# Ver3.net
KiCad netlist of a schematic drawn in EAGLE
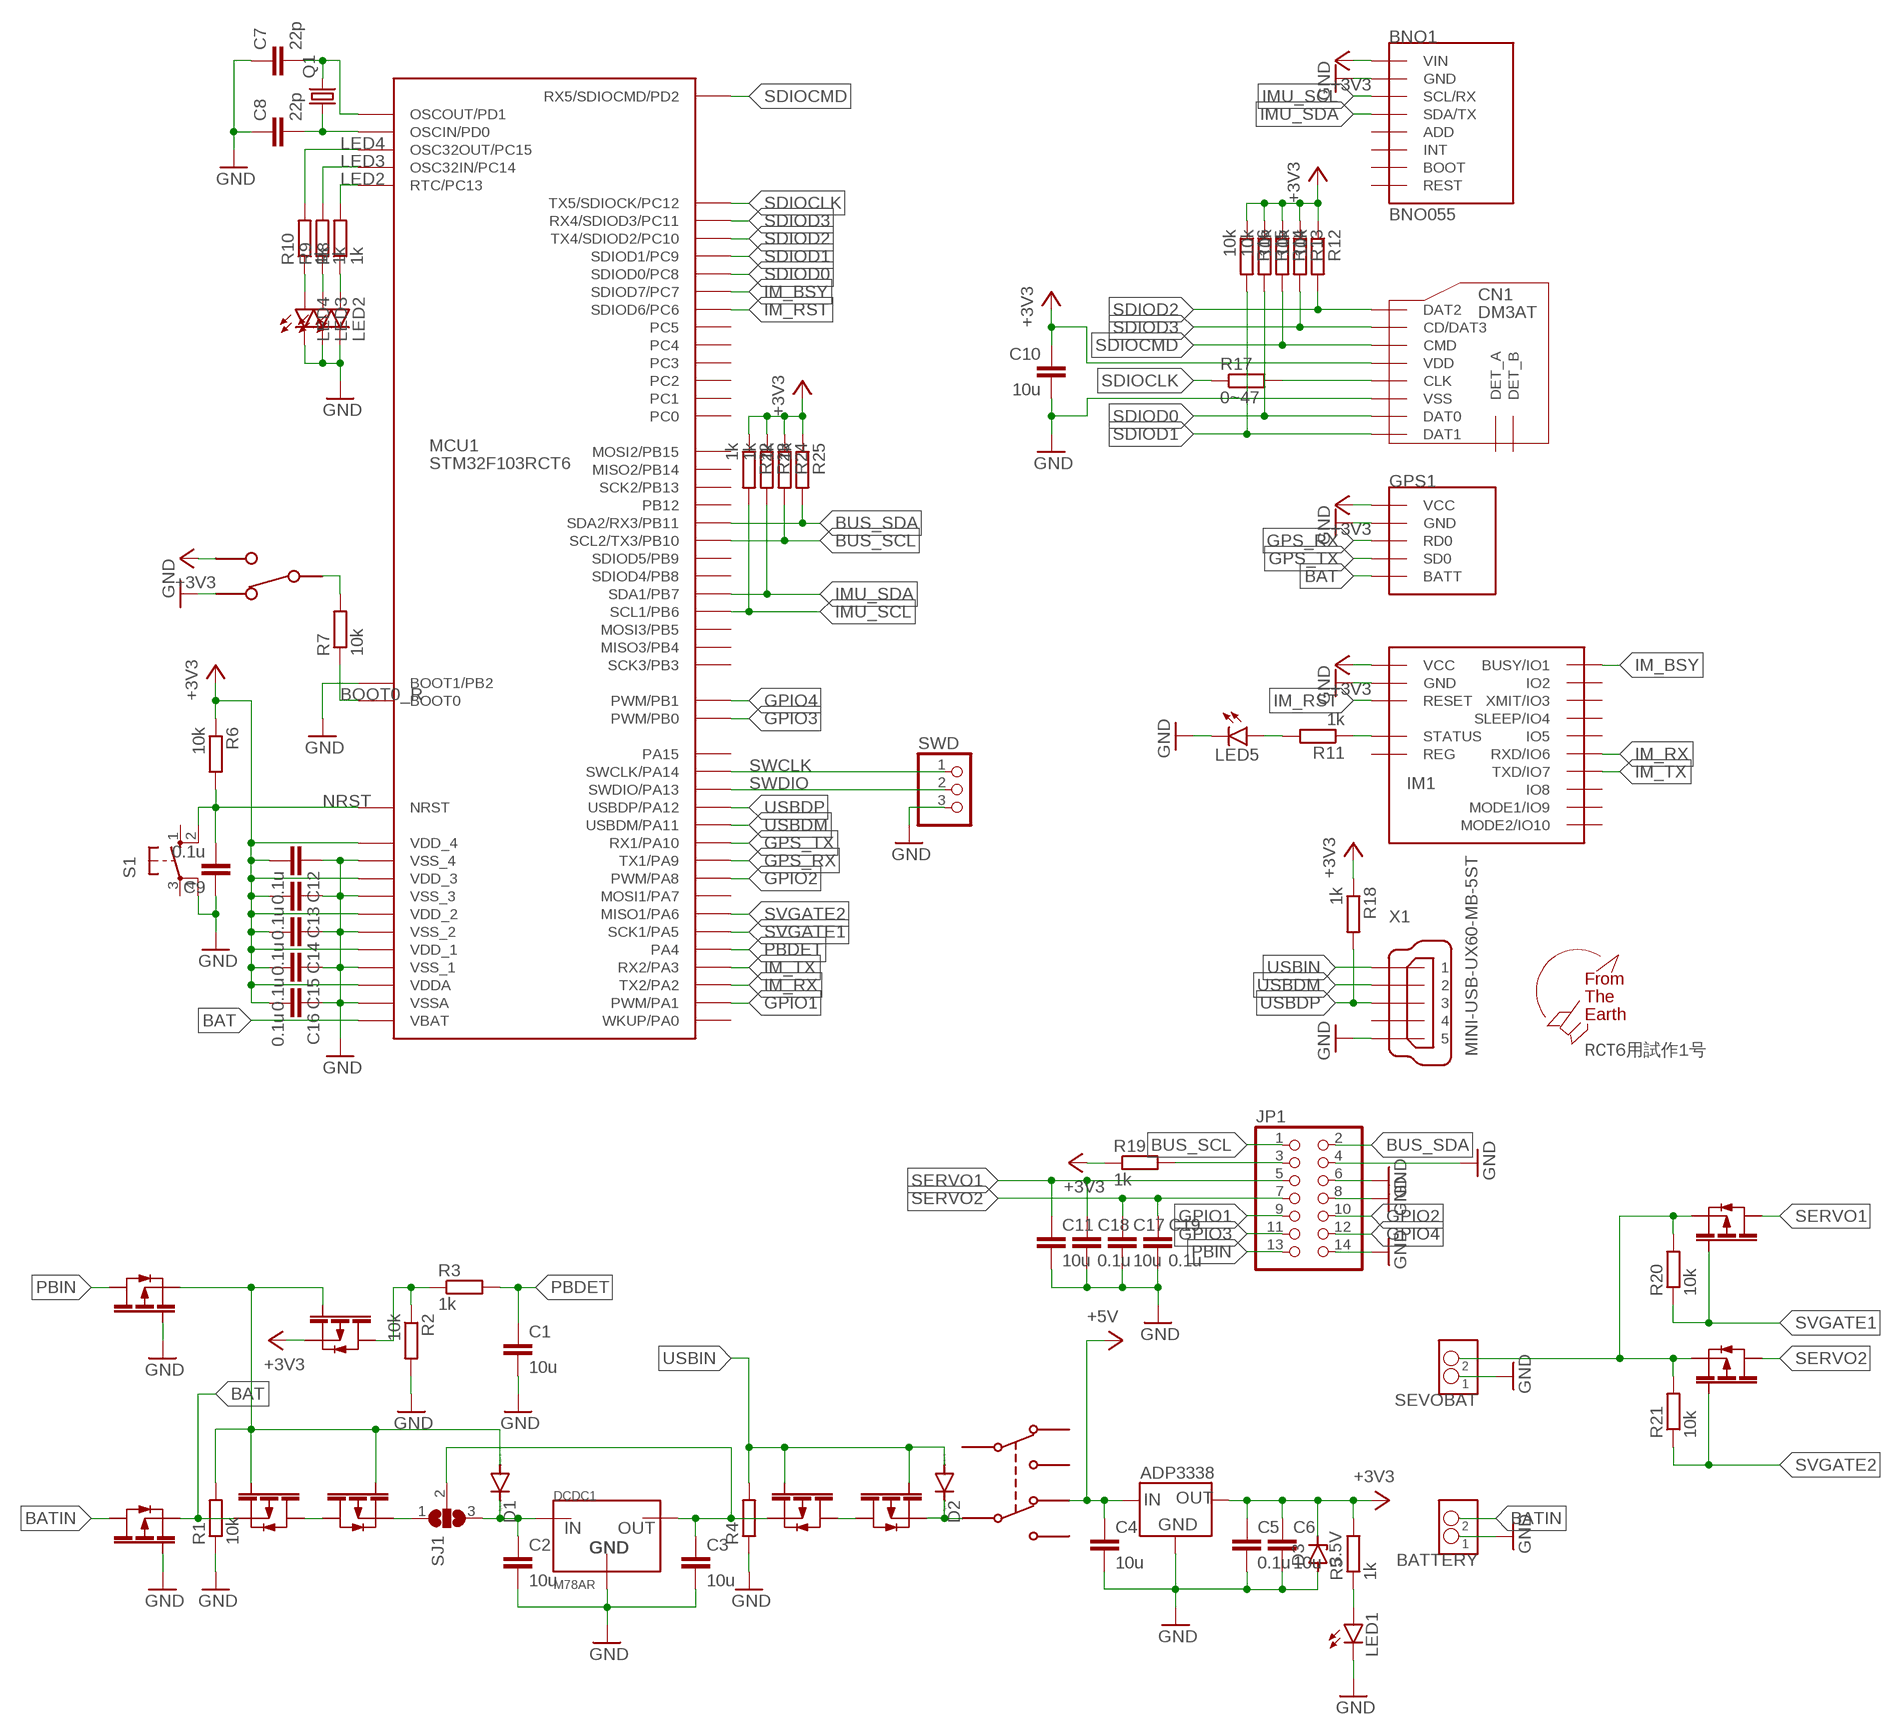
[diagram p0: schematic, sheet 1]

(export (version "E")
  (design (tool "Eeschema 10.0.6"))
  (components
    (comp (ref "BATTERY")
      (value "S2B-XH-A")
      (footprint "eagle-import:S2B-XH-A")
      (libsource (lib "eagle-import") (part "S2B-XH-A"))
    )
    (comp (ref "BNO1")
      (value "BNO055")
      (footprint "eagle-import:BNO055")
      (libsource (lib "eagle-import") (part "BNO055"))
    )
    (comp (ref "C1")
      (value "10u")
      (footprint "eagle-import:C0805")
      (libsource (lib "eagle-import") (part "C-EUC0805"))
    )
    (comp (ref "C2")
      (value "10u")
      (footprint "eagle-import:C0805")
      (libsource (lib "eagle-import") (part "C-EUC0805"))
    )
    (comp (ref "C3")
      (value "10u")
      (footprint "eagle-import:C0805")
      (libsource (lib "eagle-import") (part "C-EUC0805"))
    )
    (comp (ref "C4")
      (value "10u")
      (footprint "eagle-import:C0805")
      (libsource (lib "eagle-import") (part "C-EUC0805"))
    )
    (comp (ref "C5")
      (value "0.1u")
      (footprint "eagle-import:C0805")
      (libsource (lib "eagle-import") (part "C-EUC0805"))
    )
    (comp (ref "C6")
      (value "10u")
      (footprint "eagle-import:C0805")
      (libsource (lib "eagle-import") (part "C-EUC0805"))
    )
    (comp (ref "C7")
      (value "22p")
      (footprint "eagle-import:C0805")
      (libsource (lib "eagle-import") (part "C-EUC0805"))
    )
    (comp (ref "C8")
      (value "22p")
      (footprint "eagle-import:C0805")
      (libsource (lib "eagle-import") (part "C-EUC0805"))
    )
    (comp (ref "C9")
      (value "0.1u")
      (footprint "eagle-import:C0805")
      (libsource (lib "eagle-import") (part "C-EUC0805"))
    )
    (comp (ref "C10")
      (value "10u")
      (footprint "eagle-import:C0805")
      (libsource (lib "eagle-import") (part "C-EUC0805"))
    )
    (comp (ref "C11")
      (value "10u")
      (footprint "eagle-import:C0805")
      (libsource (lib "eagle-import") (part "C-EUC0805"))
    )
    (comp (ref "C12")
      (value "0.1u")
      (footprint "eagle-import:C0805")
      (libsource (lib "eagle-import") (part "C-EUC0805"))
    )
    (comp (ref "C13")
      (value "0.1u")
      (footprint "eagle-import:C0805")
      (libsource (lib "eagle-import") (part "C-EUC0805"))
    )
    (comp (ref "C14")
      (value "0.1u")
      (footprint "eagle-import:C0805")
      (libsource (lib "eagle-import") (part "C-EUC0805"))
    )
    (comp (ref "C15")
      (value "0.1u")
      (footprint "eagle-import:C0805")
      (libsource (lib "eagle-import") (part "C-EUC0805"))
    )
    (comp (ref "C16")
      (value "0.1u")
      (footprint "eagle-import:C0805")
      (libsource (lib "eagle-import") (part "C-EUC0805"))
    )
    (comp (ref "C17")
      (value "10u")
      (footprint "eagle-import:C0805")
      (libsource (lib "eagle-import") (part "C-EUC0805"))
    )
    (comp (ref "C18")
      (value "0.1u")
      (footprint "eagle-import:C0805")
      (libsource (lib "eagle-import") (part "C-EUC0805"))
    )
    (comp (ref "C19")
      (value "0.1u")
      (footprint "eagle-import:C0805")
      (libsource (lib "eagle-import") (part "C-EUC0805"))
    )
    (comp (ref "CN1")
      (value "DM3AT")
      (footprint "eagle-import:DM3AT")
      (libsource (lib "eagle-import") (part "DM3AT"))
    )
    (comp (ref "D1")
      (value "DIODE-SOD123")
      (footprint "eagle-import:SOD123")
      (libsource (lib "eagle-import") (part "DIODE-SOD123"))
    )
    (comp (ref "D2")
      (value "DIODE-SOD123")
      (footprint "eagle-import:SOD123")
      (libsource (lib "eagle-import") (part "DIODE-SOD123"))
    )
    (comp (ref "D3")
      (value "3.5V")
      (footprint "eagle-import:SMB")
      (libsource (lib "eagle-import") (part "ZENER-DIODESMB"))
    )
    (comp (ref "DCDC1")
      (value "M78AR")
      (footprint "eagle-import:M78AR")
      (libsource (lib "eagle-import") (part "M78AR"))
    )
    (comp (ref "FET1")
      (value "PCH")
      (footprint "eagle-import:SOT-23")
      (libsource (lib "eagle-import") (part "PCH"))
    )
    (comp (ref "FET2")
      (value "PCH")
      (footprint "eagle-import:SOT-23")
      (libsource (lib "eagle-import") (part "PCH"))
    )
    (comp (ref "FET3")
      (value "PCH")
      (footprint "eagle-import:SOT-23")
      (libsource (lib "eagle-import") (part "PCH"))
    )
    (comp (ref "FET4")
      (value "PCH")
      (footprint "eagle-import:SOT-23")
      (libsource (lib "eagle-import") (part "PCH"))
    )
    (comp (ref "FET5")
      (value "PCH")
      (footprint "eagle-import:SOT-23")
      (libsource (lib "eagle-import") (part "PCH"))
    )
    (comp (ref "FET6")
      (value "PCH")
      (footprint "eagle-import:SOT-23")
      (libsource (lib "eagle-import") (part "PCH"))
    )
    (comp (ref "FET7")
      (value "PCH")
      (footprint "eagle-import:SOT-23")
      (libsource (lib "eagle-import") (part "PCH"))
    )
    (comp (ref "FET8")
      (value "PCH")
      (footprint "eagle-import:SOT-23")
      (libsource (lib "eagle-import") (part "PCH"))
    )
    (comp (ref "FET9")
      (value "PCH")
      (footprint "eagle-import:SOT-23")
      (libsource (lib "eagle-import") (part "PCH"))
    )
    (comp (ref "GPS1")
      (value "GPS-54D")
      (footprint "eagle-import:GPS-54D")
      (libsource (lib "eagle-import") (part "GPS-54D"))
    )
    (comp (ref "IC1")
      (value "ADP3338-3.3")
      (footprint "eagle-import:SOT-223")
      (libsource (lib "eagle-import") (part "ADP3338-3.3"))
    )
    (comp (ref "IM1")
      (value "IM920C")
      (footprint "eagle-import:IM920C")
      (libsource (lib "eagle-import") (part "IM920C"))
    )
    (comp (ref "JP1")
      (value "PINHD-2X7")
      (footprint "eagle-import:2X07")
      (libsource (lib "eagle-import") (part "PINHD-2X7"))
    )
    (comp (ref "LED1")
      (value "LEDSML0603")
      (footprint "eagle-import:SML0603")
      (libsource (lib "eagle-import") (part "LEDSML0603"))
    )
    (comp (ref "LED2")
      (value "LEDSML0603")
      (footprint "eagle-import:SML0603")
      (libsource (lib "eagle-import") (part "LEDSML0603"))
    )
    (comp (ref "LED3")
      (value "LEDSML0603")
      (footprint "eagle-import:SML0603")
      (libsource (lib "eagle-import") (part "LEDSML0603"))
    )
    (comp (ref "LED4")
      (value "LEDSML0603")
      (footprint "eagle-import:SML0603")
      (libsource (lib "eagle-import") (part "LEDSML0603"))
    )
    (comp (ref "LED5")
      (value "LEDSML0603")
      (footprint "eagle-import:SML0603")
      (libsource (lib "eagle-import") (part "LEDSML0603"))
    )
    (comp (ref "MCU1")
      (value "STM32F103RCT6")
      (footprint "eagle-import:LQFP64")
      (libsource (lib "eagle-import") (part "STM32F103RCT6"))
    )
    (comp (ref "Q1")
      (value "CRYSTALHC49S")
      (footprint "eagle-import:HC49_S")
      (libsource (lib "eagle-import") (part "CRYSTALHC49S"))
    )
    (comp (ref "R1")
      (value "10k")
      (footprint "eagle-import:R0603")
      (libsource (lib "eagle-import") (part "R-EU_R0603"))
    )
    (comp (ref "R2")
      (value "10k")
      (footprint "eagle-import:R0603")
      (libsource (lib "eagle-import") (part "R-EU_R0603"))
    )
    (comp (ref "R3")
      (value "1k")
      (footprint "eagle-import:R0603")
      (libsource (lib "eagle-import") (part "R-EU_R0603"))
    )
    (comp (ref "R4")
      (value "R-EU_R0603")
      (footprint "eagle-import:R0603")
      (libsource (lib "eagle-import") (part "R-EU_R0603"))
    )
    (comp (ref "R5")
      (value "1k")
      (footprint "eagle-import:R0603")
      (libsource (lib "eagle-import") (part "R-EU_R0603"))
    )
    (comp (ref "R6")
      (value "10k")
      (footprint "eagle-import:R0603")
      (libsource (lib "eagle-import") (part "R-EU_R0603"))
    )
    (comp (ref "R7")
      (value "10k")
      (footprint "eagle-import:R0603")
      (libsource (lib "eagle-import") (part "R-EU_R0603"))
    )
    (comp (ref "R8")
      (value "1k")
      (footprint "eagle-import:R0603")
      (libsource (lib "eagle-import") (part "R-EU_R0603"))
    )
    (comp (ref "R9")
      (value "1k")
      (footprint "eagle-import:R0603")
      (libsource (lib "eagle-import") (part "R-EU_R0603"))
    )
    (comp (ref "R10")
      (value "1k")
      (footprint "eagle-import:R0603")
      (libsource (lib "eagle-import") (part "R-EU_R0603"))
    )
    (comp (ref "R11")
      (value "1k")
      (footprint "eagle-import:R0603")
      (libsource (lib "eagle-import") (part "R-EU_R0603"))
    )
    (comp (ref "R12")
      (value "10k")
      (footprint "eagle-import:R0603")
      (libsource (lib "eagle-import") (part "R-EU_R0603"))
    )
    (comp (ref "R13")
      (value "10k")
      (footprint "eagle-import:R0603")
      (libsource (lib "eagle-import") (part "R-EU_R0603"))
    )
    (comp (ref "R14")
      (value "10k")
      (footprint "eagle-import:R0603")
      (libsource (lib "eagle-import") (part "R-EU_R0603"))
    )
    (comp (ref "R15")
      (value "10k")
      (footprint "eagle-import:R0603")
      (libsource (lib "eagle-import") (part "R-EU_R0603"))
    )
    (comp (ref "R16")
      (value "10k")
      (footprint "eagle-import:R0603")
      (libsource (lib "eagle-import") (part "R-EU_R0603"))
    )
    (comp (ref "R17")
      (value "0~47")
      (footprint "eagle-import:R0603")
      (libsource (lib "eagle-import") (part "R-EU_R0603"))
    )
    (comp (ref "R18")
      (value "1k")
      (footprint "eagle-import:R0603")
      (libsource (lib "eagle-import") (part "R-EU_R0603"))
    )
    (comp (ref "R19")
      (value "1k")
      (footprint "eagle-import:R0603")
      (libsource (lib "eagle-import") (part "R-EU_R0603"))
    )
    (comp (ref "R20")
      (value "10k")
      (footprint "eagle-import:R0603")
      (libsource (lib "eagle-import") (part "R-EU_R0603"))
    )
    (comp (ref "R21")
      (value "10k")
      (footprint "eagle-import:R0603")
      (libsource (lib "eagle-import") (part "R-EU_R0603"))
    )
    (comp (ref "R22")
      (value "1k")
      (footprint "eagle-import:R0603")
      (libsource (lib "eagle-import") (part "R-EU_R0603"))
    )
    (comp (ref "R23")
      (value "1k")
      (footprint "eagle-import:R0603")
      (libsource (lib "eagle-import") (part "R-EU_R0603"))
    )
    (comp (ref "R24")
      (value "1k")
      (footprint "eagle-import:R0603")
      (libsource (lib "eagle-import") (part "R-EU_R0603"))
    )
    (comp (ref "R25")
      (value "1k")
      (footprint "eagle-import:R0603")
      (libsource (lib "eagle-import") (part "R-EU_R0603"))
    )
    (comp (ref "RCT6用試作1号")
      (value "F.T.E.LOGO")
      (footprint "eagle-import:LOGO")
      (libsource (lib "eagle-import") (part "F.T.E.LOGO"))
    )
    (comp (ref "S1")
      (value "10-XX")
      (footprint "eagle-import:B3F-10XX")
      (fields (field (name "MPN") "B3F-1000"))
      (libsource (lib "eagle-import") (part "10-XX"))
    )
    (comp (ref "SEVOBAT")
      (value "S2B-XH-A")
      (footprint "eagle-import:S2B-XH-A")
      (libsource (lib "eagle-import") (part "S2B-XH-A"))
    )
    (comp (ref "SJ1")
      (value "SJ2W")
      (footprint "eagle-import:SJ_2")
      (libsource (lib "eagle-import") (part "SJ2W"))
    )
    (comp (ref "SWD")
      (value "PINHD-1X3/90")
      (footprint "eagle-import:1X03_90")
      (libsource (lib "eagle-import") (part "PINHD-1X3/90"))
    )
    (comp (ref "U$2")
      (value "SSSS213202")
      (footprint "eagle-import:SMD_6P")
      (libsource (lib "eagle-import") (part "SSSS213202"))
    )
    (comp (ref "U$3")
      (value "MSS22D18")
      (footprint "eagle-import:MSS22D18")
      (libsource (lib "eagle-import") (part "MSS22D18"))
    )
    (comp (ref "X1")
      (value "MINI-USB-UX60-MB-5ST")
      (footprint "eagle-import:UX60-MB-5ST")
      (libsource (lib "eagle-import") (part "MINI-USB-UX60-MB-5ST"))
    )
  )
  (nets
    (net (code "1") (name "+3V3") (class "Default")
      (node (ref "BNO1") (pin "P1") (pinfunction "VIN_P1") (pintype "bidirectional"))
      (node (ref "C10") (pin "1") (pinfunction "1_1") (pintype "passive"))
      (node (ref "C12") (pin "2") (pinfunction "2_2") (pintype "passive"))
      (node (ref "C13") (pin "2") (pinfunction "2_2") (pintype "passive"))
      (node (ref "C14") (pin "2") (pinfunction "2_2") (pintype "passive"))
      (node (ref "C15") (pin "2") (pinfunction "2_2") (pintype "passive"))
      (node (ref "C16") (pin "2") (pinfunction "2_2") (pintype "passive"))
      (node (ref "C5") (pin "1") (pinfunction "1_1") (pintype "passive"))
      (node (ref "C6") (pin "1") (pinfunction "1_1") (pintype "passive"))
      (node (ref "CN1") (pin "VDD") (pinfunction "VDD_VDD") (pintype "bidirectional"))
      (node (ref "D3") (pin "C") (pinfunction "C_C") (pintype "passive"))
      (node (ref "FET5") (pin "P$2") (pinfunction "P$2_P$2") (pintype "bidirectional"))
      (node (ref "GPS1") (pin "VCC") (pinfunction "VCC_VCC") (pintype "bidirectional"))
      (node (ref "IC1") (pin "1") (pinfunction "OUT_1") (pintype "output"))
      (node (ref "IC1") (pin "2") (pinfunction "OUT_2") (pintype "output"))
      (node (ref "IM1") (pin "$P17") (pinfunction "VCC_$P17") (pintype "bidirectional"))
      (node (ref "MCU1") (pin "P$13") (pinfunction "VDDA_P$13") (pintype "bidirectional"))
      (node (ref "MCU1") (pin "P$19") (pinfunction "VDD_4_P$19") (pintype "bidirectional"))
      (node (ref "MCU1") (pin "P$32") (pinfunction "VDD_1_P$32") (pintype "bidirectional"))
      (node (ref "MCU1") (pin "P$48") (pinfunction "VDD_2_P$48") (pintype "bidirectional"))
      (node (ref "MCU1") (pin "P$64") (pinfunction "VDD_3_P$64") (pintype "bidirectional"))
      (node (ref "R12") (pin "1") (pinfunction "1_1") (pintype "passive"))
      (node (ref "R13") (pin "1") (pinfunction "1_1") (pintype "passive"))
      (node (ref "R14") (pin "1") (pinfunction "1_1") (pintype "passive"))
      (node (ref "R15") (pin "1") (pinfunction "1_1") (pintype "passive"))
      (node (ref "R16") (pin "1") (pinfunction "1_1") (pintype "passive"))
      (node (ref "R18") (pin "1") (pinfunction "1_1") (pintype "passive"))
      (node (ref "R19") (pin "1") (pinfunction "1_1") (pintype "passive"))
      (node (ref "R22") (pin "1") (pinfunction "1_1") (pintype "passive"))
      (node (ref "R23") (pin "1") (pinfunction "1_1") (pintype "passive"))
      (node (ref "R24") (pin "1") (pinfunction "1_1") (pintype "passive"))
      (node (ref "R25") (pin "1") (pinfunction "1_1") (pintype "passive"))
      (node (ref "R5") (pin "2") (pinfunction "2_2") (pintype "passive"))
      (node (ref "R6") (pin "1") (pinfunction "1_1") (pintype "passive"))
      (node (ref "U$2") (pin "P$0") (pinfunction "PD1_P$0") (pintype "bidirectional"))
      (node (ref "U$2") (pin "P$5") (pinfunction "PD1_P$5") (pintype "bidirectional"))
    )
    (net (code "2") (name "+5V") (class "Default")
      (node (ref "C4") (pin "1") (pinfunction "1_1") (pintype "passive"))
      (node (ref "IC1") (pin "3") (pinfunction "IN_3") (pintype "input"))
      (node (ref "U$3") (pin "P$2") (pinfunction "P$3_P$2") (pintype "bidirectional"))
    )
    (net (code "3") (name "/BOOT0_R") (class "Default")
      (node (ref "MCU1") (pin "P$60") (pinfunction "BOOT0_P$60") (pintype "bidirectional"))
      (node (ref "R7") (pin "1") (pinfunction "1_1") (pintype "passive"))
    )
    (net (code "4") (name "/LED2") (class "Default")
      (node (ref "MCU1") (pin "P$2") (pinfunction "RTC/PC13_P$2") (pintype "bidirectional"))
      (node (ref "R8") (pin "2") (pinfunction "2_2") (pintype "passive"))
    )
    (net (code "5") (name "/LED3") (class "Default")
      (node (ref "MCU1") (pin "P$3") (pinfunction "OSC32IN/PC14_P$3") (pintype "bidirectional"))
      (node (ref "R9") (pin "2") (pinfunction "2_2") (pintype "passive"))
    )
    (net (code "6") (name "/LED4") (class "Default")
      (node (ref "MCU1") (pin "P$4") (pinfunction "OSC32OUT/PC15_P$4") (pintype "bidirectional"))
      (node (ref "R10") (pin "2") (pinfunction "2_2") (pintype "passive"))
    )
    (net (code "7") (name "/NRST") (class "Default")
      (node (ref "C9") (pin "2") (pinfunction "2_2") (pintype "passive"))
      (node (ref "MCU1") (pin "P$7") (pinfunction "NRST_P$7") (pintype "bidirectional"))
      (node (ref "R6") (pin "2") (pinfunction "2_2") (pintype "passive"))
      (node (ref "S1") (pin "2") (pinfunction "S1_2") (pintype "passive"))
    )
    (net (code "8") (name "/SWCLK") (class "Default")
      (node (ref "MCU1") (pin "P$49") (pinfunction "SWCLK/PA14_P$49") (pintype "bidirectional"))
      (node (ref "SWD") (pin "1") (pinfunction "1_1") (pintype "passive"))
    )
    (net (code "9") (name "/SWDIO") (class "Default")
      (node (ref "MCU1") (pin "P$46") (pinfunction "SWDIO/PA13_P$46") (pintype "bidirectional"))
      (node (ref "SWD") (pin "2") (pinfunction "2_2") (pintype "passive"))
    )
    (net (code "10") (name "BAT") (class "Default")
      (node (ref "FET1") (pin "P$2") (pinfunction "P$2_P$2") (pintype "bidirectional"))
      (node (ref "FET3") (pin "P$2") (pinfunction "P$2_P$2") (pintype "bidirectional"))
      (node (ref "GPS1") (pin "BATT") (pinfunction "BATT_BATT") (pintype "bidirectional"))
      (node (ref "MCU1") (pin "P$1") (pinfunction "VBAT_P$1") (pintype "bidirectional"))
    )
    (net (code "11") (name "BATIN") (class "Default")
      (node (ref "BATTERY") (pin "P$2") (pinfunction "2_P$2") (pintype "bidirectional"))
      (node (ref "FET1") (pin "P$3") (pinfunction "P$3_P$3") (pintype "bidirectional"))
    )
    (net (code "12") (name "BUS_SCL") (class "Default")
      (node (ref "JP1") (pin "1") (pinfunction "1_1") (pintype "passive"))
      (node (ref "MCU1") (pin "P$29") (pinfunction "SCL2/TX3/PB10_P$29") (pintype "bidirectional"))
      (node (ref "R24") (pin "2") (pinfunction "2_2") (pintype "passive"))
    )
    (net (code "13") (name "BUS_SDA") (class "Default")
      (node (ref "JP1") (pin "2") (pinfunction "2_2") (pintype "passive"))
      (node (ref "MCU1") (pin "P$30") (pinfunction "SDA2/RX3/PB11_P$30") (pintype "bidirectional"))
      (node (ref "R25") (pin "2") (pinfunction "2_2") (pintype "passive"))
    )
    (net (code "14") (name "GND") (class "Default")
      (node (ref "BATTERY") (pin "P$1") (pinfunction "1_P$1") (pintype "bidirectional"))
      (node (ref "BNO1") (pin "P2") (pinfunction "GND_P2") (pintype "bidirectional"))
      (node (ref "C1") (pin "2") (pinfunction "2_2") (pintype "passive"))
      (node (ref "C10") (pin "2") (pinfunction "2_2") (pintype "passive"))
      (node (ref "C11") (pin "2") (pinfunction "2_2") (pintype "passive"))
      (node (ref "C12") (pin "1") (pinfunction "1_1") (pintype "passive"))
      (node (ref "C13") (pin "1") (pinfunction "1_1") (pintype "passive"))
      (node (ref "C14") (pin "1") (pinfunction "1_1") (pintype "passive"))
      (node (ref "C15") (pin "1") (pinfunction "1_1") (pintype "passive"))
      (node (ref "C16") (pin "1") (pinfunction "1_1") (pintype "passive"))
      (node (ref "C17") (pin "2") (pinfunction "2_2") (pintype "passive"))
      (node (ref "C18") (pin "2") (pinfunction "2_2") (pintype "passive"))
      (node (ref "C19") (pin "2") (pinfunction "2_2") (pintype "passive"))
      (node (ref "C2") (pin "2") (pinfunction "2_2") (pintype "passive"))
      (node (ref "C3") (pin "2") (pinfunction "2_2") (pintype "passive"))
      (node (ref "C4") (pin "2") (pinfunction "2_2") (pintype "passive"))
      (node (ref "C5") (pin "2") (pinfunction "2_2") (pintype "passive"))
      (node (ref "C6") (pin "2") (pinfunction "2_2") (pintype "passive"))
      (node (ref "C7") (pin "1") (pinfunction "1_1") (pintype "passive"))
      (node (ref "C8") (pin "1") (pinfunction "1_1") (pintype "passive"))
      (node (ref "C9") (pin "1") (pinfunction "1_1") (pintype "passive"))
      (node (ref "CN1") (pin "VSS") (pinfunction "VSS_VSS") (pintype "bidirectional"))
      (node (ref "D3") (pin "A") (pinfunction "A_A") (pintype "passive"))
      (node (ref "DCDC1") (pin "P2") (pinfunction "GND_P2") (pintype "bidirectional"))
      (node (ref "FET1") (pin "P$1") (pinfunction "P$1_P$1") (pintype "bidirectional"))
      (node (ref "FET4") (pin "P$1") (pinfunction "P$1_P$1") (pintype "bidirectional"))
      (node (ref "GPS1") (pin "GND") (pinfunction "GND_GND") (pintype "bidirectional"))
      (node (ref "IC1") (pin "4") (pinfunction "GND_4") (pintype "bidirectional"))
      (node (ref "IM1") (pin "$P18") (pinfunction "GND_$P18") (pintype "bidirectional"))
      (node (ref "JP1") (pin "14") (pinfunction "14_14") (pintype "passive"))
      (node (ref "JP1") (pin "4") (pinfunction "4_4") (pintype "passive"))
      (node (ref "JP1") (pin "6") (pinfunction "6_6") (pintype "passive"))
      (node (ref "JP1") (pin "8") (pinfunction "8_8") (pintype "passive"))
      (node (ref "LED1") (pin "C") (pinfunction "C_C") (pintype "passive"))
      (node (ref "LED2") (pin "C") (pinfunction "C_C") (pintype "passive"))
      (node (ref "LED3") (pin "C") (pinfunction "C_C") (pintype "passive"))
      (node (ref "LED4") (pin "C") (pinfunction "C_C") (pintype "passive"))
      (node (ref "LED5") (pin "C") (pinfunction "C_C") (pintype "passive"))
      (node (ref "MCU1") (pin "P$12") (pinfunction "VSSA_P$12") (pintype "bidirectional"))
      (node (ref "MCU1") (pin "P$18") (pinfunction "VSS_4_P$18") (pintype "bidirectional"))
      (node (ref "MCU1") (pin "P$28") (pinfunction "BOOT1/PB2_P$28") (pintype "bidirectional"))
      (node (ref "MCU1") (pin "P$31") (pinfunction "VSS_1_P$31") (pintype "bidirectional"))
      (node (ref "MCU1") (pin "P$47") (pinfunction "VSS_2_P$47") (pintype "bidirectional"))
      (node (ref "MCU1") (pin "P$63") (pinfunction "VSS_3_P$63") (pintype "bidirectional"))
      (node (ref "R1") (pin "1") (pinfunction "1_1") (pintype "passive"))
      (node (ref "R2") (pin "2") (pinfunction "2_2") (pintype "passive"))
      (node (ref "R4") (pin "1") (pinfunction "1_1") (pintype "passive"))
      (node (ref "S1") (pin "4") (pinfunction "P1_4") (pintype "passive"))
      (node (ref "SEVOBAT") (pin "P$1") (pinfunction "1_P$1") (pintype "bidirectional"))
      (node (ref "SWD") (pin "3") (pinfunction "3_3") (pintype "passive"))
      (node (ref "U$2") (pin "P$2") (pinfunction "PD3_P$2") (pintype "bidirectional"))
      (node (ref "U$2") (pin "P$3") (pinfunction "PD3_P$3") (pintype "bidirectional"))
      (node (ref "X1") (pin "5") (pinfunction "5_5") (pintype "input"))
    )
    (net (code "15") (name "GPIO1") (class "Default")
      (node (ref "JP1") (pin "9") (pinfunction "9_9") (pintype "passive"))
      (node (ref "MCU1") (pin "P$15") (pinfunction "PWM/PA1_P$15") (pintype "bidirectional"))
    )
    (net (code "16") (name "GPIO2") (class "Default")
      (node (ref "JP1") (pin "10") (pinfunction "10_10") (pintype "passive"))
      (node (ref "MCU1") (pin "P$41") (pinfunction "PWM/PA8_P$41") (pintype "bidirectional"))
    )
    (net (code "17") (name "GPIO3") (class "Default")
      (node (ref "JP1") (pin "11") (pinfunction "11_11") (pintype "passive"))
      (node (ref "MCU1") (pin "P$26") (pinfunction "PWM/PB0_P$26") (pintype "bidirectional"))
    )
    (net (code "18") (name "GPIO4") (class "Default")
      (node (ref "JP1") (pin "12") (pinfunction "12_12") (pintype "passive"))
      (node (ref "MCU1") (pin "P$27") (pinfunction "PWM/PB1_P$27") (pintype "bidirectional"))
    )
    (net (code "19") (name "GPS_RX") (class "Default")
      (node (ref "GPS1") (pin "RD0") (pinfunction "RD0_RD0") (pintype "bidirectional"))
      (node (ref "MCU1") (pin "P$42") (pinfunction "TX1/PA9_P$42") (pintype "bidirectional"))
    )
    (net (code "20") (name "GPS_TX") (class "Default")
      (node (ref "GPS1") (pin "SD0") (pinfunction "SD0_SD0") (pintype "bidirectional"))
      (node (ref "MCU1") (pin "P$43") (pinfunction "RX1/PA10_P$43") (pintype "bidirectional"))
    )
    (net (code "21") (name "IMU_SCL") (class "Default")
      (node (ref "BNO1") (pin "P3") (pinfunction "SCL/RX_P3") (pintype "bidirectional"))
      (node (ref "MCU1") (pin "P$58") (pinfunction "SCL1/PB6_P$58") (pintype "bidirectional"))
      (node (ref "R22") (pin "2") (pinfunction "2_2") (pintype "passive"))
    )
    (net (code "22") (name "IMU_SDA") (class "Default")
      (node (ref "BNO1") (pin "P4") (pinfunction "SDA/TX_P4") (pintype "bidirectional"))
      (node (ref "MCU1") (pin "P$59") (pinfunction "SDA1/PB7_P$59") (pintype "bidirectional"))
      (node (ref "R23") (pin "2") (pinfunction "2_2") (pintype "passive"))
    )
    (net (code "23") (name "IM_BSY") (class "Default")
      (node (ref "IM1") (pin "$P1") (pinfunction "BUSY/IO1_$P1") (pintype "bidirectional"))
      (node (ref "MCU1") (pin "P$38") (pinfunction "SDIOD7/PC7_P$38") (pintype "bidirectional"))
    )
    (net (code "24") (name "IM_RST") (class "Default")
      (node (ref "IM1") (pin "$P19") (pinfunction "RESET_$P19") (pintype "bidirectional"))
      (node (ref "MCU1") (pin "P$37") (pinfunction "SDIOD6/PC6_P$37") (pintype "bidirectional"))
    )
    (net (code "25") (name "IM_RX") (class "Default")
      (node (ref "IM1") (pin "$P6") (pinfunction "RXD/IO6_$P6") (pintype "bidirectional"))
      (node (ref "MCU1") (pin "P$16") (pinfunction "TX2/PA2_P$16") (pintype "bidirectional"))
    )
    (net (code "26") (name "IM_TX") (class "Default")
      (node (ref "IM1") (pin "$P7") (pinfunction "TXD/IO7_$P7") (pintype "bidirectional"))
      (node (ref "MCU1") (pin "P$17") (pinfunction "RX2/PA3_P$17") (pintype "bidirectional"))
    )
    (net (code "27") (name "Net-(CN1-PadCLK)") (class "Default")
      (node (ref "CN1") (pin "CLK") (pinfunction "CLK_CLK") (pintype "bidirectional"))
      (node (ref "R17") (pin "2") (pinfunction "2_2") (pintype "passive"))
    )
    (net (code "28") (name "Net-(D1-PadA)") (class "Default")
      (node (ref "D1") (pin "A") (pinfunction "A_A") (pintype "passive"))
      (node (ref "FET2") (pin "P$1") (pinfunction "P$1_P$1") (pintype "bidirectional"))
      (node (ref "FET3") (pin "P$1") (pinfunction "P$1_P$1") (pintype "bidirectional"))
      (node (ref "FET4") (pin "P$2") (pinfunction "P$2_P$2") (pintype "bidirectional"))
      (node (ref "FET5") (pin "P$1") (pinfunction "P$1_P$1") (pintype "bidirectional"))
      (node (ref "R1") (pin "2") (pinfunction "2_2") (pintype "passive"))
    )
    (net (code "29") (name "Net-(DCDC1-IN)") (class "Default")
      (node (ref "C2") (pin "1") (pinfunction "1_1") (pintype "passive"))
      (node (ref "D1") (pin "C") (pinfunction "C_C") (pintype "passive"))
      (node (ref "DCDC1") (pin "P3") (pinfunction "IN_P3") (pintype "bidirectional"))
      (node (ref "SJ1") (pin "3") (pinfunction "3_3") (pintype "passive"))
    )
    (net (code "30") (name "Net-(DCDC1-OUT)") (class "Default")
      (node (ref "C3") (pin "1") (pinfunction "1_1") (pintype "passive"))
      (node (ref "DCDC1") (pin "P1") (pinfunction "OUT_P1") (pintype "bidirectional"))
      (node (ref "FET6") (pin "P$2") (pinfunction "P$2_P$2") (pintype "bidirectional"))
      (node (ref "SJ1") (pin "2") (pinfunction "2_2") (pintype "passive"))
    )
    (net (code "31") (name "Net-(FET2-PadP$2)") (class "Default")
      (node (ref "FET2") (pin "P$2") (pinfunction "P$2_P$2") (pintype "bidirectional"))
      (node (ref "SJ1") (pin "1") (pinfunction "1_1") (pintype "passive"))
    )
    (net (code "32") (name "Net-(FET2-PadP$3)") (class "Default")
      (node (ref "FET2") (pin "P$3") (pinfunction "P$3_P$3") (pintype "bidirectional"))
      (node (ref "FET3") (pin "P$3") (pinfunction "P$3_P$3") (pintype "bidirectional"))
    )
    (net (code "33") (name "Net-(FET5-PadP$3)") (class "Default")
      (node (ref "FET5") (pin "P$3") (pinfunction "P$3_P$3") (pintype "bidirectional"))
      (node (ref "R2") (pin "1") (pinfunction "1_1") (pintype "passive"))
      (node (ref "R3") (pin "1") (pinfunction "1_1") (pintype "passive"))
    )
    (net (code "34") (name "Net-(FET6-PadP$3)") (class "Default")
      (node (ref "FET6") (pin "P$3") (pinfunction "P$3_P$3") (pintype "bidirectional"))
      (node (ref "FET7") (pin "P$3") (pinfunction "P$3_P$3") (pintype "bidirectional"))
    )
    (net (code "35") (name "Net-(IM1-STATUS)") (class "Default")
      (node (ref "IM1") (pin "$P15") (pinfunction "STATUS_$P15") (pintype "bidirectional"))
      (node (ref "R11") (pin "1") (pinfunction "1_1") (pintype "passive"))
    )
    (net (code "36") (name "Net-(JP1-Pad3)") (class "Default")
      (node (ref "JP1") (pin "3") (pinfunction "3_3") (pintype "passive"))
      (node (ref "R19") (pin "2") (pinfunction "2_2") (pintype "passive"))
    )
    (net (code "37") (name "Net-(LED1-PadA)") (class "Default")
      (node (ref "LED1") (pin "A") (pinfunction "A_A") (pintype "passive"))
      (node (ref "R5") (pin "1") (pinfunction "1_1") (pintype "passive"))
    )
    (net (code "38") (name "Net-(LED2-PadA)") (class "Default")
      (node (ref "LED2") (pin "A") (pinfunction "A_A") (pintype "passive"))
      (node (ref "R8") (pin "1") (pinfunction "1_1") (pintype "passive"))
    )
    (net (code "39") (name "Net-(LED3-PadA)") (class "Default")
      (node (ref "LED3") (pin "A") (pinfunction "A_A") (pintype "passive"))
      (node (ref "R9") (pin "1") (pinfunction "1_1") (pintype "passive"))
    )
    (net (code "40") (name "Net-(LED4-PadA)") (class "Default")
      (node (ref "LED4") (pin "A") (pinfunction "A_A") (pintype "passive"))
      (node (ref "R10") (pin "1") (pinfunction "1_1") (pintype "passive"))
    )
    (net (code "41") (name "Net-(LED5-PadA)") (class "Default")
      (node (ref "LED5") (pin "A") (pinfunction "A_A") (pintype "passive"))
      (node (ref "R11") (pin "2") (pinfunction "2_2") (pintype "passive"))
    )
    (net (code "42") (name "Net-(MCU1-OSCIN{slash}PD0)") (class "Default")
      (node (ref "C8") (pin "2") (pinfunction "2_2") (pintype "passive"))
      (node (ref "MCU1") (pin "P$5") (pinfunction "OSCIN/PD0_P$5") (pintype "bidirectional"))
      (node (ref "Q1") (pin "1") (pinfunction "1_1") (pintype "passive"))
    )
    (net (code "43") (name "Net-(MCU1-OSCOUT{slash}PD1)") (class "Default")
      (node (ref "C7") (pin "2") (pinfunction "2_2") (pintype "passive"))
      (node (ref "MCU1") (pin "P$6") (pinfunction "OSCOUT/PD1_P$6") (pintype "bidirectional"))
      (node (ref "Q1") (pin "2") (pinfunction "2_2") (pintype "passive"))
    )
    (net (code "44") (name "Net-(R7-Pad2)") (class "Default")
      (node (ref "R7") (pin "2") (pinfunction "2_2") (pintype "passive"))
      (node (ref "U$2") (pin "P$1") (pinfunction "PD2_P$1") (pintype "bidirectional"))
      (node (ref "U$2") (pin "P$4") (pinfunction "PD2_P$4") (pintype "bidirectional"))
    )
    (net (code "45") (name "Net-(SEVOBAT-2)") (class "Default")
      (node (ref "FET8") (pin "P$2") (pinfunction "P$2_P$2") (pintype "bidirectional"))
      (node (ref "FET9") (pin "P$2") (pinfunction "P$2_P$2") (pintype "bidirectional"))
      (node (ref "R20") (pin "2") (pinfunction "2_2") (pintype "passive"))
      (node (ref "R21") (pin "2") (pinfunction "2_2") (pintype "passive"))
      (node (ref "SEVOBAT") (pin "P$2") (pinfunction "2_P$2") (pintype "bidirectional"))
    )
    (net (code "46") (name "Net-(U$3-P$2)") (class "Default")
      (node (ref "D2") (pin "C") (pinfunction "C_C") (pintype "passive"))
      (node (ref "FET7") (pin "P$2") (pinfunction "P$2_P$2") (pintype "bidirectional"))
      (node (ref "U$3") (pin "P$1") (pinfunction "P$2_P$1") (pintype "bidirectional"))
    )
    (net (code "47") (name "PBDET") (class "Default")
      (node (ref "C1") (pin "1") (pinfunction "1_1") (pintype "passive"))
      (node (ref "MCU1") (pin "P$20") (pinfunction "PA4_P$20") (pintype "bidirectional"))
      (node (ref "R3") (pin "2") (pinfunction "2_2") (pintype "passive"))
    )
    (net (code "48") (name "PBIN") (class "Default")
      (node (ref "FET4") (pin "P$3") (pinfunction "P$3_P$3") (pintype "bidirectional"))
      (node (ref "JP1") (pin "13") (pinfunction "13_13") (pintype "passive"))
    )
    (net (code "49") (name "SDIOCLK") (class "Default")
      (node (ref "MCU1") (pin "P$53") (pinfunction "TX5/SDIOCK/PC12_P$53") (pintype "bidirectional"))
      (node (ref "R17") (pin "1") (pinfunction "1_1") (pintype "passive"))
    )
    (net (code "50") (name "SDIOCMD") (class "Default")
      (node (ref "CN1") (pin "CMD") (pinfunction "CMD_CMD") (pintype "bidirectional"))
      (node (ref "MCU1") (pin "P$54") (pinfunction "RX5/SDIOCMD/PD2_P$54") (pintype "bidirectional"))
      (node (ref "R14") (pin "2") (pinfunction "2_2") (pintype "passive"))
    )
    (net (code "51") (name "SDIOD0") (class "Default")
      (node (ref "CN1") (pin "DAT0") (pinfunction "DAT0_DAT0") (pintype "bidirectional"))
      (node (ref "MCU1") (pin "P$39") (pinfunction "SDIOD0/PC8_P$39") (pintype "bidirectional"))
      (node (ref "R15") (pin "2") (pinfunction "2_2") (pintype "passive"))
    )
    (net (code "52") (name "SDIOD1") (class "Default")
      (node (ref "CN1") (pin "DAT1") (pinfunction "DAT1_DAT1") (pintype "bidirectional"))
      (node (ref "MCU1") (pin "P$40") (pinfunction "SDIOD1/PC9_P$40") (pintype "bidirectional"))
      (node (ref "R16") (pin "2") (pinfunction "2_2") (pintype "passive"))
    )
    (net (code "53") (name "SDIOD2") (class "Default")
      (node (ref "CN1") (pin "DAT2") (pinfunction "DAT2_DAT2") (pintype "bidirectional"))
      (node (ref "MCU1") (pin "P$51") (pinfunction "TX4/SDIOD2/PC10_P$51") (pintype "bidirectional"))
      (node (ref "R12") (pin "2") (pinfunction "2_2") (pintype "passive"))
    )
    (net (code "54") (name "SDIOD3") (class "Default")
      (node (ref "CN1") (pin "CD/DAT3") (pinfunction "CD/DAT3_CD/DAT3") (pintype "bidirectional"))
      (node (ref "MCU1") (pin "P$52") (pinfunction "RX4/SDIOD3/PC11_P$52") (pintype "bidirectional"))
      (node (ref "R13") (pin "2") (pinfunction "2_2") (pintype "passive"))
    )
    (net (code "55") (name "SERVO1") (class "Default")
      (node (ref "C11") (pin "1") (pinfunction "1_1") (pintype "passive"))
      (node (ref "C18") (pin "1") (pinfunction "1_1") (pintype "passive"))
      (node (ref "FET8") (pin "P$3") (pinfunction "P$3_P$3") (pintype "bidirectional"))
      (node (ref "JP1") (pin "5") (pinfunction "5_5") (pintype "passive"))
    )
    (net (code "56") (name "SERVO2") (class "Default")
      (node (ref "C17") (pin "1") (pinfunction "1_1") (pintype "passive"))
      (node (ref "C19") (pin "1") (pinfunction "1_1") (pintype "passive"))
      (node (ref "FET9") (pin "P$3") (pinfunction "P$3_P$3") (pintype "bidirectional"))
      (node (ref "JP1") (pin "7") (pinfunction "7_7") (pintype "passive"))
    )
    (net (code "57") (name "SVGATE1") (class "Default")
      (node (ref "FET8") (pin "P$1") (pinfunction "P$1_P$1") (pintype "bidirectional"))
      (node (ref "MCU1") (pin "P$21") (pinfunction "SCK1/PA5_P$21") (pintype "bidirectional"))
      (node (ref "R20") (pin "1") (pinfunction "1_1") (pintype "passive"))
    )
    (net (code "58") (name "SVGATE2") (class "Default")
      (node (ref "FET9") (pin "P$1") (pinfunction "P$1_P$1") (pintype "bidirectional"))
      (node (ref "MCU1") (pin "P$22") (pinfunction "MISO1/PA6_P$22") (pintype "bidirectional"))
      (node (ref "R21") (pin "1") (pinfunction "1_1") (pintype "passive"))
    )
    (net (code "59") (name "USBDM") (class "Default")
      (node (ref "MCU1") (pin "P$44") (pinfunction "USBDM/PA11_P$44") (pintype "bidirectional"))
      (node (ref "X1") (pin "2") (pinfunction "2_2") (pintype "input"))
    )
    (net (code "60") (name "USBDP") (class "Default")
      (node (ref "MCU1") (pin "P$45") (pinfunction "USBDP/PA12_P$45") (pintype "bidirectional"))
      (node (ref "R18") (pin "2") (pinfunction "2_2") (pintype "passive"))
      (node (ref "X1") (pin "3") (pinfunction "3_3") (pintype "input"))
    )
    (net (code "61") (name "USBIN") (class "Default")
      (node (ref "D2") (pin "A") (pinfunction "A_A") (pintype "passive"))
      (node (ref "FET6") (pin "P$1") (pinfunction "P$1_P$1") (pintype "bidirectional"))
      (node (ref "FET7") (pin "P$1") (pinfunction "P$1_P$1") (pintype "bidirectional"))
      (node (ref "R4") (pin "2") (pinfunction "2_2") (pintype "passive"))
      (node (ref "X1") (pin "1") (pinfunction "1_1") (pintype "input"))
    )
    (net (code "62") (name "unconnected-(BNO1-ADD-PadP5)") (class "Default")
      (node (ref "BNO1") (pin "P5") (pinfunction "ADD_P5") (pintype "bidirectional"))
    )
    (net (code "63") (name "unconnected-(BNO1-BOOT-PadP7)") (class "Default")
      (node (ref "BNO1") (pin "P7") (pinfunction "BOOT_P7") (pintype "bidirectional"))
    )
    (net (code "64") (name "unconnected-(BNO1-INT-PadP6)") (class "Default")
      (node (ref "BNO1") (pin "P6") (pinfunction "INT_P6") (pintype "bidirectional"))
    )
    (net (code "65") (name "unconnected-(BNO1-REST-PadP8)") (class "Default")
      (node (ref "BNO1") (pin "P8") (pinfunction "REST_P8") (pintype "bidirectional"))
    )
    (net (code "66") (name "unconnected-(CN1-PadDET_A)") (class "Default")
      (node (ref "CN1") (pin "DET_A") (pinfunction "DET_A_DET_A") (pintype "bidirectional"))
    )
    (net (code "67") (name "unconnected-(CN1-PadDET_B)") (class "Default")
      (node (ref "CN1") (pin "DET_B") (pinfunction "DET_B_DET_B") (pintype "bidirectional"))
    )
    (net (code "68") (name "unconnected-(IM1-IO2-Pad$P2)") (class "Default")
      (node (ref "IM1") (pin "$P2") (pinfunction "IO2_$P2") (pintype "bidirectional"))
    )
    (net (code "69") (name "unconnected-(IM1-IO5-Pad$P5)") (class "Default")
      (node (ref "IM1") (pin "$P5") (pinfunction "IO5_$P5") (pintype "bidirectional"))
    )
    (net (code "70") (name "unconnected-(IM1-IO8-Pad$P8)") (class "Default")
      (node (ref "IM1") (pin "$P8") (pinfunction "IO8_$P8") (pintype "bidirectional"))
    )
    (net (code "71") (name "unconnected-(IM1-MODE1{slash}IO9-Pad$P9)") (class "Default")
      (node (ref "IM1") (pin "$P9") (pinfunction "MODE1/IO9_$P9") (pintype "bidirectional"))
    )
    (net (code "72") (name "unconnected-(IM1-MODE2{slash}IO10-Pad$P10)") (class "Default")
      (node (ref "IM1") (pin "$P10") (pinfunction "MODE2/IO10_$P10") (pintype "bidirectional"))
    )
    (net (code "73") (name "unconnected-(IM1-REG-Pad$P16)") (class "Default")
      (node (ref "IM1") (pin "$P16") (pinfunction "REG_$P16") (pintype "bidirectional"))
    )
    (net (code "74") (name "unconnected-(IM1-SLEEP{slash}IO4-Pad$P4)") (class "Default")
      (node (ref "IM1") (pin "$P4") (pinfunction "SLEEP/IO4_$P4") (pintype "bidirectional"))
    )
    (net (code "75") (name "unconnected-(IM1-XMIT{slash}IO3-Pad$P3)") (class "Default")
      (node (ref "IM1") (pin "$P3") (pinfunction "XMIT/IO3_$P3") (pintype "bidirectional"))
    )
    (net (code "76") (name "unconnected-(MCU1-MISO2{slash}PB14-PadP$35)") (class "Default")
      (node (ref "MCU1") (pin "P$35") (pinfunction "MISO2/PB14_P$35") (pintype "bidirectional"))
    )
    (net (code "77") (name "unconnected-(MCU1-MISO3{slash}PB4-PadP$56)") (class "Default")
      (node (ref "MCU1") (pin "P$56") (pinfunction "MISO3/PB4_P$56") (pintype "bidirectional"))
    )
    (net (code "78") (name "unconnected-(MCU1-MOSI1{slash}PA7-PadP$23)") (class "Default")
      (node (ref "MCU1") (pin "P$23") (pinfunction "MOSI1/PA7_P$23") (pintype "bidirectional"))
    )
    (net (code "79") (name "unconnected-(MCU1-MOSI2{slash}PB15-PadP$36)") (class "Default")
      (node (ref "MCU1") (pin "P$36") (pinfunction "MOSI2/PB15_P$36") (pintype "bidirectional"))
    )
    (net (code "80") (name "unconnected-(MCU1-MOSI3{slash}PB5-PadP$57)") (class "Default")
      (node (ref "MCU1") (pin "P$57") (pinfunction "MOSI3/PB5_P$57") (pintype "bidirectional"))
    )
    (net (code "81") (name "unconnected-(MCU1-PA15-PadP$50)") (class "Default")
      (node (ref "MCU1") (pin "P$50") (pinfunction "PA15_P$50") (pintype "bidirectional"))
    )
    (net (code "82") (name "unconnected-(MCU1-PB12-PadP$33)") (class "Default")
      (node (ref "MCU1") (pin "P$33") (pinfunction "PB12_P$33") (pintype "bidirectional"))
    )
    (net (code "83") (name "unconnected-(MCU1-PC0-PadP$8)") (class "Default")
      (node (ref "MCU1") (pin "P$8") (pinfunction "PC0_P$8") (pintype "bidirectional"))
    )
    (net (code "84") (name "unconnected-(MCU1-PC1-PadP$9)") (class "Default")
      (node (ref "MCU1") (pin "P$9") (pinfunction "PC1_P$9") (pintype "bidirectional"))
    )
    (net (code "85") (name "unconnected-(MCU1-PC2-PadP$10)") (class "Default")
      (node (ref "MCU1") (pin "P$10") (pinfunction "PC2_P$10") (pintype "bidirectional"))
    )
    (net (code "86") (name "unconnected-(MCU1-PC3-PadP$11)") (class "Default")
      (node (ref "MCU1") (pin "P$11") (pinfunction "PC3_P$11") (pintype "bidirectional"))
    )
    (net (code "87") (name "unconnected-(MCU1-PC4-PadP$24)") (class "Default")
      (node (ref "MCU1") (pin "P$24") (pinfunction "PC4_P$24") (pintype "bidirectional"))
    )
    (net (code "88") (name "unconnected-(MCU1-PC5-PadP$25)") (class "Default")
      (node (ref "MCU1") (pin "P$25") (pinfunction "PC5_P$25") (pintype "bidirectional"))
    )
    (net (code "89") (name "unconnected-(MCU1-SCK2{slash}PB13-PadP$34)") (class "Default")
      (node (ref "MCU1") (pin "P$34") (pinfunction "SCK2/PB13_P$34") (pintype "bidirectional"))
    )
    (net (code "90") (name "unconnected-(MCU1-SCK3{slash}PB3-PadP$55)") (class "Default")
      (node (ref "MCU1") (pin "P$55") (pinfunction "SCK3/PB3_P$55") (pintype "bidirectional"))
    )
    (net (code "91") (name "unconnected-(MCU1-SDIOD4{slash}PB8-PadP$61)") (class "Default")
      (node (ref "MCU1") (pin "P$61") (pinfunction "SDIOD4/PB8_P$61") (pintype "bidirectional"))
    )
    (net (code "92") (name "unconnected-(MCU1-SDIOD5{slash}PB9-PadP$62)") (class "Default")
      (node (ref "MCU1") (pin "P$62") (pinfunction "SDIOD5/PB9_P$62") (pintype "bidirectional"))
    )
    (net (code "93") (name "unconnected-(MCU1-WKUP{slash}PA0-PadP$14)") (class "Default")
      (node (ref "MCU1") (pin "P$14") (pinfunction "WKUP/PA0_P$14") (pintype "bidirectional"))
    )
    (net (code "94") (name "unconnected-(S1-P-Pad3)") (class "Default")
      (node (ref "S1") (pin "3") (pinfunction "P_3") (pintype "passive"))
    )
    (net (code "95") (name "unconnected-(S1-S-Pad1)") (class "Default")
      (node (ref "S1") (pin "1") (pinfunction "S_1") (pintype "passive"))
    )
    (net (code "96") (name "unconnected-(U$3-P$1-PadP$0)") (class "Default")
      (node (ref "U$3") (pin "P$0") (pinfunction "P$1_P$0") (pintype "bidirectional"))
    )
    (net (code "97") (name "unconnected-(U$3-P$4-PadP$5)") (class "Default")
      (node (ref "U$3") (pin "P$5") (pinfunction "P$4_P$5") (pintype "bidirectional"))
    )
    (net (code "98") (name "unconnected-(U$3-P$5-PadP$4)") (class "Default")
      (node (ref "U$3") (pin "P$4") (pinfunction "P$5_P$4") (pintype "bidirectional"))
    )
    (net (code "99") (name "unconnected-(U$3-P$6-PadP$3)") (class "Default")
      (node (ref "U$3") (pin "P$3") (pinfunction "P$6_P$3") (pintype "bidirectional"))
    )
    (net (code "100") (name "unconnected-(X1-Pad4)") (class "Default")
      (node (ref "X1") (pin "4") (pinfunction "4_4") (pintype "input"))
    )
  )
)
